# NMEA_BatteryMonitor_1-2.net
KiCad netlist of a schematic drawn in EAGLE
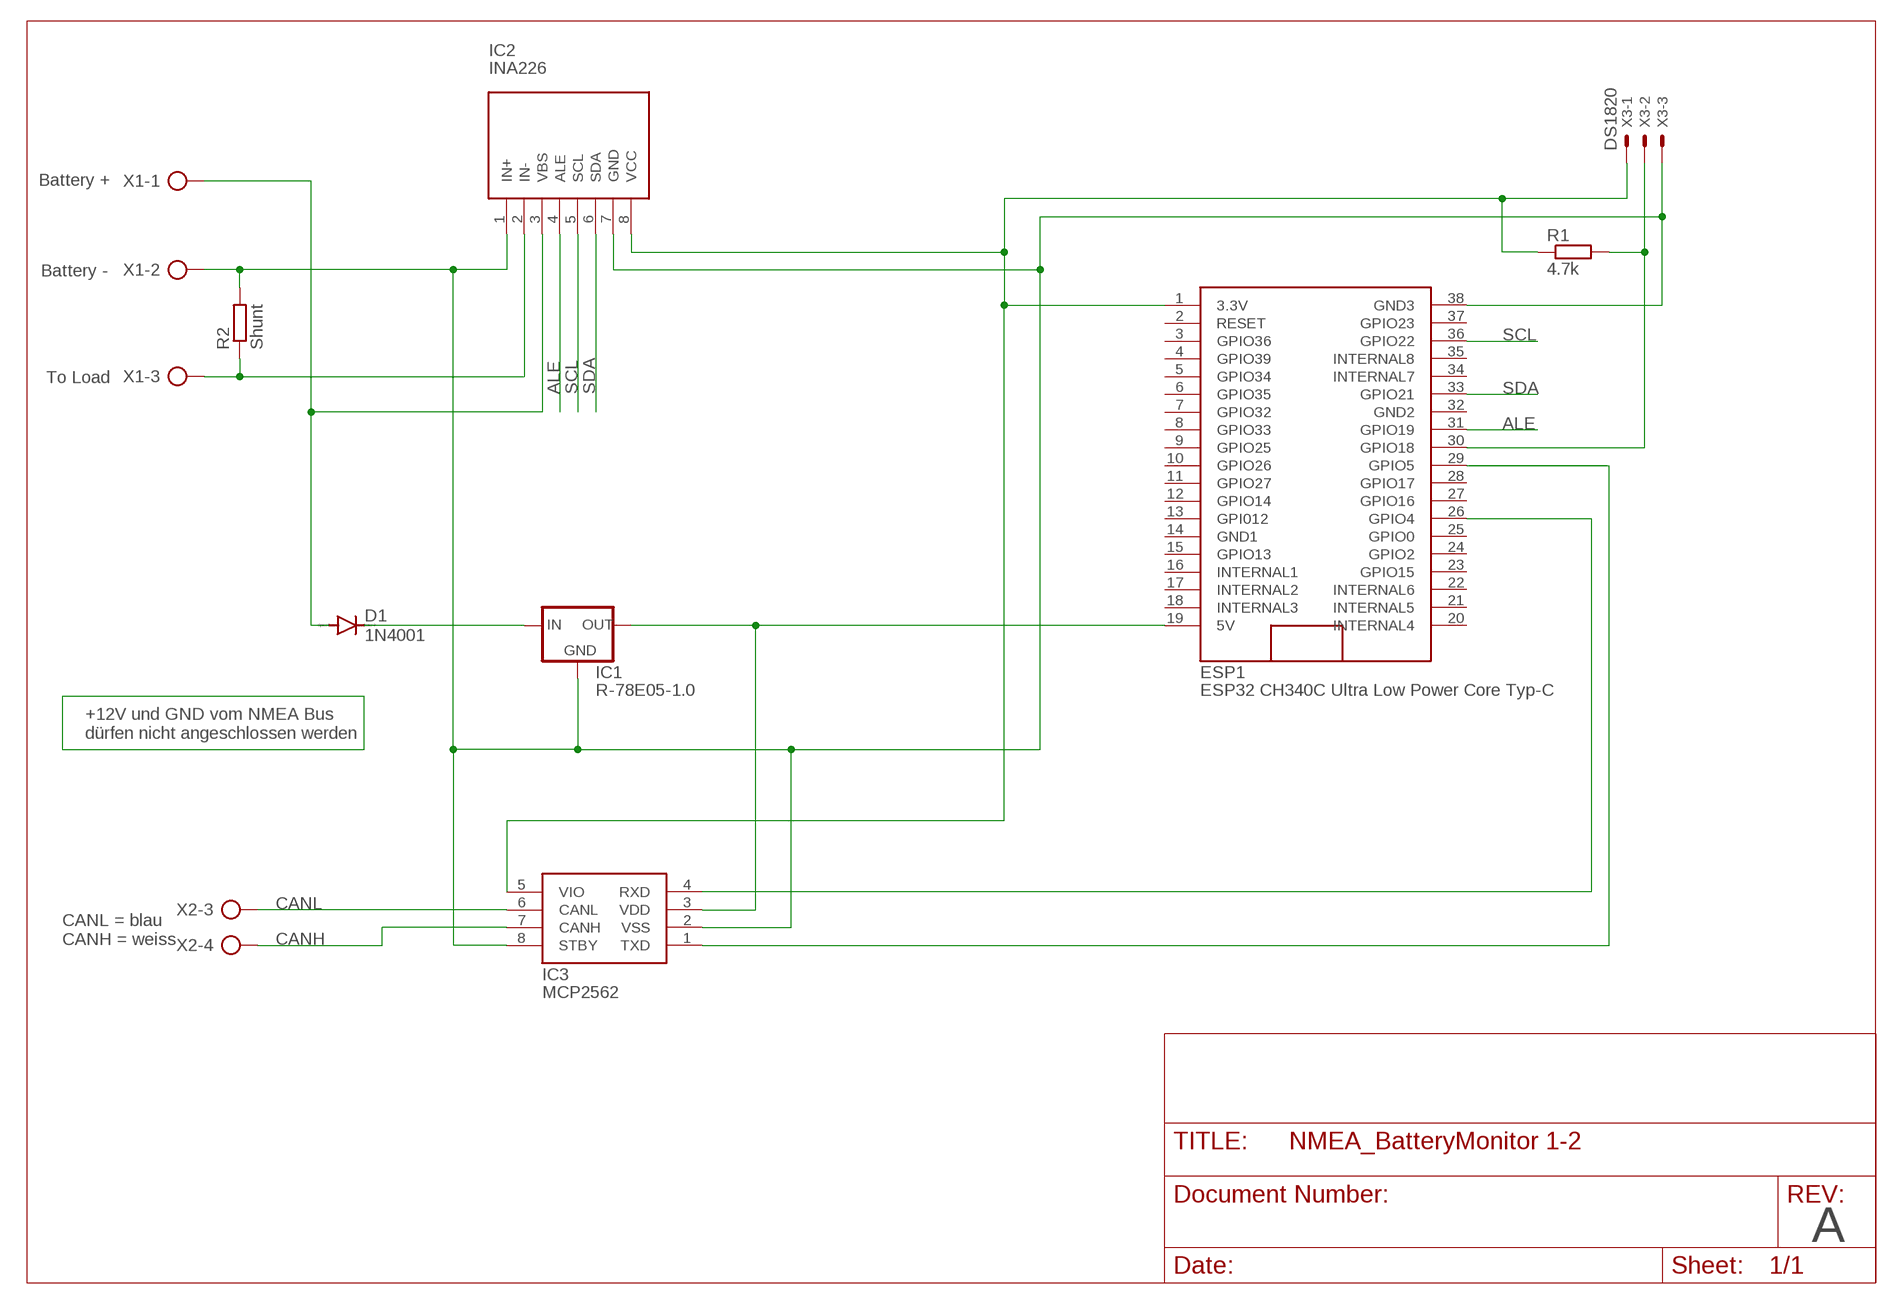
[diagram p0: schematic, sheet 1]

(export (version "E")
  (design (tool "Eeschema 10.0.6"))
  (components
    (comp (ref "D1")
      (value "1N4001")
      (footprint "eagle-import:DO41-10")
      (libsource (lib "eagle-import") (part "1N4004"))
    )
    (comp (ref "ESP1")
      (value "ESP32 CH340C Ultra Low Power Core Typ-C")
      (footprint "eagle-import:ESP32_NODEMCU")
      (libsource (lib "eagle-import") (part "ESP32-NODEMCU"))
    )
    (comp (ref "IC1")
      (value "R-78E05-1.0")
      (footprint "eagle-import:78XXS")
      (libsource (lib "eagle-import") (part "78XXS"))
    )
    (comp (ref "IC2")
      (value "INA226")
      (footprint "eagle-import:INA226")
      (libsource (lib "eagle-import") (part "INA226"))
    )
    (comp (ref "IC3")
      (value "MCP2562")
      (footprint "eagle-import:DIL08")
      (libsource (lib "eagle-import") (part "MCP2562"))
    )
    (comp (ref "R1")
      (value "4.7k")
      (footprint "eagle-import:0207_7")
      (libsource (lib "eagle-import") (part "R-EU_0207/7"))
    )
    (comp (ref "R2")
      (value "Shunt")
      (footprint "eagle-import:0309_12")
      (libsource (lib "eagle-import") (part "R-EU_0309/12"))
    )
    (comp (ref "X1")
      (value "AK500/5")
      (footprint "eagle-import:AK500_5")
      (libsource (lib "eagle-import") (part "AK500/5"))
    )
    (comp (ref "X2")
      (value "AK500/5")
      (footprint "eagle-import:AK500_5")
      (libsource (lib "eagle-import") (part "AK500/5"))
    )
    (comp (ref "X3")
      (value "DS1820")
      (footprint "eagle-import:22-23-2031")
      (fields (field (name "MF") "MOLEX") (field (name "MPN") "22-23-2031"))
      (libsource (lib "eagle-import") (part "22-23-2031"))
    )
  )
  (nets
    (net (code "1") (name "/ALE") (class "Default")
      (node (ref "ESP1") (pin "31") (pinfunction "GPIO19_31") (pintype "bidirectional"))
      (node (ref "IC2") (pin "4") (pinfunction "ALE_4") (pintype "bidirectional"))
    )
    (net (code "2") (name "/CANH") (class "Default")
      (node (ref "IC3") (pin "7") (pinfunction "CANH_7") (pintype "bidirectional"))
      (node (ref "X2") (pin "4") (pinfunction "KL_4") (pintype "passive"))
    )
    (net (code "3") (name "/CANL") (class "Default")
      (node (ref "IC3") (pin "6") (pinfunction "CANL_6") (pintype "bidirectional"))
      (node (ref "X2") (pin "3") (pinfunction "KL_3") (pintype "passive"))
    )
    (net (code "4") (name "/GND1") (class "Default")
      (node (ref "ESP1") (pin "14") (pinfunction "GND1_14") (pintype "power_in"))
    )
    (net (code "5") (name "/GND2") (class "Default")
      (node (ref "ESP1") (pin "32") (pinfunction "GND2_32") (pintype "power_in"))
    )
    (net (code "6") (name "/SCL") (class "Default")
      (node (ref "ESP1") (pin "36") (pinfunction "GPIO22_36") (pintype "bidirectional"))
      (node (ref "IC2") (pin "5") (pinfunction "SCL_5") (pintype "bidirectional"))
    )
    (net (code "7") (name "/SDA") (class "Default")
      (node (ref "ESP1") (pin "33") (pinfunction "GPIO21_33") (pintype "bidirectional"))
      (node (ref "IC2") (pin "6") (pinfunction "SDA_6") (pintype "bidirectional"))
    )
    (net (code "8") (name "Net-(D1-PadC)") (class "Default")
      (node (ref "D1") (pin "C") (pinfunction "C_C") (pintype "passive"))
      (node (ref "IC1") (pin "IN") (pinfunction "IN_IN") (pintype "input"))
    )
    (net (code "9") (name "Net-(ESP1-3.3V)") (class "Default")
      (node (ref "ESP1") (pin "1") (pinfunction "3.3V_1") (pintype "power_in"))
      (node (ref "IC2") (pin "8") (pinfunction "VCC_8") (pintype "power_in"))
      (node (ref "IC3") (pin "5") (pinfunction "VIO_5") (pintype "bidirectional"))
      (node (ref "R1") (pin "1") (pinfunction "1_1") (pintype "passive"))
      (node (ref "X3") (pin "1") (pinfunction "S_1") (pintype "passive"))
    )
    (net (code "10") (name "Net-(ESP1-5V)") (class "Default")
      (node (ref "ESP1") (pin "19") (pinfunction "5V_19") (pintype "power_in"))
      (node (ref "IC1") (pin "OUT") (pinfunction "OUT_OUT") (pintype "passive"))
      (node (ref "IC3") (pin "3") (pinfunction "VDD_3") (pintype "bidirectional"))
    )
    (net (code "11") (name "Net-(ESP1-GND3)") (class "Default")
      (node (ref "ESP1") (pin "38") (pinfunction "GND3_38") (pintype "power_in"))
      (node (ref "IC1") (pin "GND") (pinfunction "GND_GND") (pintype "input"))
      (node (ref "IC2") (pin "1") (pinfunction "IN+_1") (pintype "bidirectional"))
      (node (ref "IC2") (pin "7") (pinfunction "GND_7") (pintype "power_in"))
      (node (ref "IC3") (pin "2") (pinfunction "VSS_2") (pintype "bidirectional"))
      (node (ref "IC3") (pin "8") (pinfunction "STBY_8") (pintype "bidirectional"))
      (node (ref "R2") (pin "2") (pinfunction "2_2") (pintype "passive"))
      (node (ref "X1") (pin "2") (pinfunction "KL_2") (pintype "passive"))
      (node (ref "X3") (pin "3") (pinfunction "S_3") (pintype "passive"))
    )
    (net (code "12") (name "Net-(ESP1-GPIO4)") (class "Default")
      (node (ref "ESP1") (pin "26") (pinfunction "GPIO4_26") (pintype "bidirectional"))
      (node (ref "IC3") (pin "4") (pinfunction "RXD_4") (pintype "bidirectional"))
    )
    (net (code "13") (name "Net-(ESP1-GPIO5)") (class "Default")
      (node (ref "ESP1") (pin "29") (pinfunction "GPIO5_29") (pintype "bidirectional"))
      (node (ref "IC3") (pin "1") (pinfunction "TXD_1") (pintype "bidirectional"))
    )
    (net (code "14") (name "Net-(ESP1-GPIO18)") (class "Default")
      (node (ref "ESP1") (pin "30") (pinfunction "GPIO18_30") (pintype "bidirectional"))
      (node (ref "R1") (pin "2") (pinfunction "2_2") (pintype "passive"))
      (node (ref "X3") (pin "2") (pinfunction "S_2") (pintype "passive"))
    )
    (net (code "15") (name "Net-(IC2-IN-)") (class "Default")
      (node (ref "IC2") (pin "2") (pinfunction "IN-_2") (pintype "bidirectional"))
      (node (ref "R2") (pin "1") (pinfunction "1_1") (pintype "passive"))
      (node (ref "X1") (pin "3") (pinfunction "KL_3") (pintype "passive"))
    )
    (net (code "16") (name "Net-(IC2-VBS)") (class "Default")
      (node (ref "D1") (pin "A") (pinfunction "A_A") (pintype "passive"))
      (node (ref "IC2") (pin "3") (pinfunction "VBS_3") (pintype "bidirectional"))
      (node (ref "X1") (pin "1") (pinfunction "KL_1") (pintype "passive"))
    )
    (net (code "17") (name "unconnected-(ESP1-GPI012-Pad13)") (class "Default")
      (node (ref "ESP1") (pin "13") (pinfunction "GPI012_13") (pintype "bidirectional"))
    )
    (net (code "18") (name "unconnected-(ESP1-GPIO0-Pad25)") (class "Default")
      (node (ref "ESP1") (pin "25") (pinfunction "GPIO0_25") (pintype "output"))
    )
    (net (code "19") (name "unconnected-(ESP1-GPIO2-Pad24)") (class "Default")
      (node (ref "ESP1") (pin "24") (pinfunction "GPIO2_24") (pintype "bidirectional"))
    )
    (net (code "20") (name "unconnected-(ESP1-GPIO13-Pad15)") (class "Default")
      (node (ref "ESP1") (pin "15") (pinfunction "GPIO13_15") (pintype "bidirectional"))
    )
    (net (code "21") (name "unconnected-(ESP1-GPIO14-Pad12)") (class "Default")
      (node (ref "ESP1") (pin "12") (pinfunction "GPIO14_12") (pintype "bidirectional"))
    )
    (net (code "22") (name "unconnected-(ESP1-GPIO15-Pad23)") (class "Default")
      (node (ref "ESP1") (pin "23") (pinfunction "GPIO15_23") (pintype "bidirectional"))
    )
    (net (code "23") (name "unconnected-(ESP1-GPIO16-Pad27)") (class "Default")
      (node (ref "ESP1") (pin "27") (pinfunction "GPIO16_27") (pintype "bidirectional"))
    )
    (net (code "24") (name "unconnected-(ESP1-GPIO17-Pad28)") (class "Default")
      (node (ref "ESP1") (pin "28") (pinfunction "GPIO17_28") (pintype "bidirectional"))
    )
    (net (code "25") (name "unconnected-(ESP1-GPIO23-Pad37)") (class "Default")
      (node (ref "ESP1") (pin "37") (pinfunction "GPIO23_37") (pintype "bidirectional"))
    )
    (net (code "26") (name "unconnected-(ESP1-GPIO25-Pad9)") (class "Default")
      (node (ref "ESP1") (pin "9") (pinfunction "GPIO25_9") (pintype "bidirectional"))
    )
    (net (code "27") (name "unconnected-(ESP1-GPIO26-Pad10)") (class "Default")
      (node (ref "ESP1") (pin "10") (pinfunction "GPIO26_10") (pintype "bidirectional"))
    )
    (net (code "28") (name "unconnected-(ESP1-GPIO27-Pad11)") (class "Default")
      (node (ref "ESP1") (pin "11") (pinfunction "GPIO27_11") (pintype "bidirectional"))
    )
    (net (code "29") (name "unconnected-(ESP1-GPIO32-Pad7)") (class "Default")
      (node (ref "ESP1") (pin "7") (pinfunction "GPIO32_7") (pintype "bidirectional"))
    )
    (net (code "30") (name "unconnected-(ESP1-GPIO33-Pad8)") (class "Default")
      (node (ref "ESP1") (pin "8") (pinfunction "GPIO33_8") (pintype "bidirectional"))
    )
    (net (code "31") (name "unconnected-(ESP1-GPIO34-Pad5)") (class "Default")
      (node (ref "ESP1") (pin "5") (pinfunction "GPIO34_5") (pintype "input"))
    )
    (net (code "32") (name "unconnected-(ESP1-GPIO35-Pad6)") (class "Default")
      (node (ref "ESP1") (pin "6") (pinfunction "GPIO35_6") (pintype "input"))
    )
    (net (code "33") (name "unconnected-(ESP1-GPIO36-Pad3)") (class "Default")
      (node (ref "ESP1") (pin "3") (pinfunction "GPIO36_3") (pintype "input"))
    )
    (net (code "34") (name "unconnected-(ESP1-GPIO39-Pad4)") (class "Default")
      (node (ref "ESP1") (pin "4") (pinfunction "GPIO39_4") (pintype "input"))
    )
    (net (code "35") (name "unconnected-(ESP1-INTERNAL1-Pad16)") (class "Default")
      (node (ref "ESP1") (pin "16") (pinfunction "INTERNAL1_16") (pintype "no_connect"))
    )
    (net (code "36") (name "unconnected-(ESP1-INTERNAL2-Pad17)") (class "Default")
      (node (ref "ESP1") (pin "17") (pinfunction "INTERNAL2_17") (pintype "no_connect"))
    )
    (net (code "37") (name "unconnected-(ESP1-INTERNAL3-Pad18)") (class "Default")
      (node (ref "ESP1") (pin "18") (pinfunction "INTERNAL3_18") (pintype "no_connect"))
    )
    (net (code "38") (name "unconnected-(ESP1-INTERNAL4-Pad20)") (class "Default")
      (node (ref "ESP1") (pin "20") (pinfunction "INTERNAL4_20") (pintype "no_connect"))
    )
    (net (code "39") (name "unconnected-(ESP1-INTERNAL5-Pad21)") (class "Default")
      (node (ref "ESP1") (pin "21") (pinfunction "INTERNAL5_21") (pintype "no_connect"))
    )
    (net (code "40") (name "unconnected-(ESP1-INTERNAL6-Pad22)") (class "Default")
      (node (ref "ESP1") (pin "22") (pinfunction "INTERNAL6_22") (pintype "no_connect"))
    )
    (net (code "41") (name "unconnected-(ESP1-INTERNAL7-Pad34)") (class "Default")
      (node (ref "ESP1") (pin "34") (pinfunction "INTERNAL7_34") (pintype "no_connect"))
    )
    (net (code "42") (name "unconnected-(ESP1-INTERNAL8-Pad35)") (class "Default")
      (node (ref "ESP1") (pin "35") (pinfunction "INTERNAL8_35") (pintype "no_connect"))
    )
    (net (code "43") (name "unconnected-(ESP1-RESET-Pad2)") (class "Default")
      (node (ref "ESP1") (pin "2") (pinfunction "RESET_2") (pintype "input"))
    )
  )
)
